# Sensor_Glove_Main-X02.net
KiCad netlist of a schematic drawn in Altium Designer
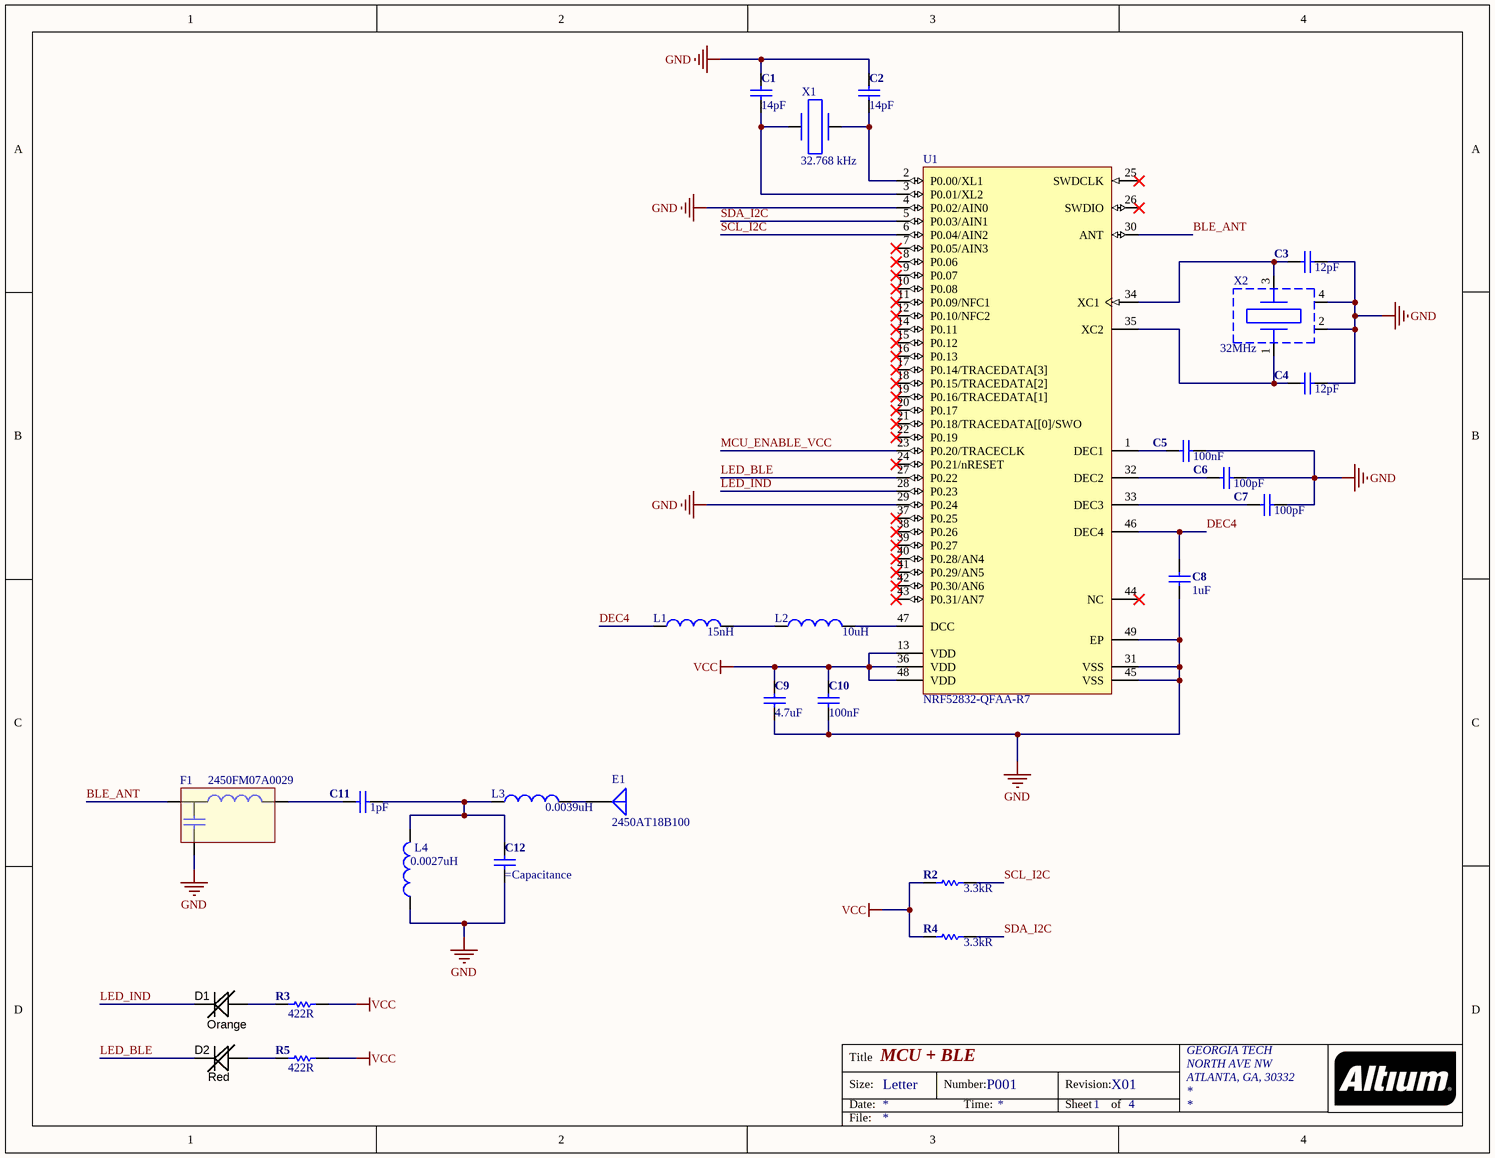
[diagram p0: Sensor_Glove_Main-X02.SchDoc]

(export (version "E")
  (design (tool "Eeschema 10.0.6"))
  (components
    (comp (ref "C1")
      (value "14pF")
      (footprint "C0402")
      (fields
        (field (name "MANUFACTURER") "Kyocera AVX")
        (field (name "MANUFACTURER PART NUMBER") "04025U140FAT2A")
        (field (name "TOLERANCE") "1%")
      )
      (libsource (lib "DB-X01") (part "C-0402(1005)"))
    )
    (comp (ref "C2")
      (value "14pF")
      (footprint "C0402")
      (fields
        (field (name "MANUFACTURER") "Kyocera AVX")
        (field (name "MANUFACTURER PART NUMBER") "04025U140FAT2A")
        (field (name "TOLERANCE") "1%")
      )
      (libsource (lib "DB-X01") (part "C-0402(1005)"))
    )
    (comp (ref "C3")
      (value "12pF")
      (footprint "C0402")
      (fields
        (field (name "MANUFACTURER") "Kyocera AVX")
        (field (name "MANUFACTURER PART NUMBER") "04025U120FAT2A")
        (field (name "TOLERANCE") "1%")
      )
      (libsource (lib "DB-X01") (part "C-0402(1005)"))
    )
    (comp (ref "C4")
      (value "12pF")
      (footprint "C0402")
      (fields
        (field (name "MANUFACTURER") "Kyocera AVX")
        (field (name "MANUFACTURER PART NUMBER") "04025U120FAT2A")
        (field (name "TOLERANCE") "1%")
      )
      (libsource (lib "DB-X01") (part "C-0402(1005)"))
    )
    (comp (ref "C5")
      (value "100nF")
      (footprint "C0402")
      (fields
        (field (name "MANUFACTURER") "Taiyo Yuden")
        (field (name "MANUFACTURER PART NUMBER") "TMK105BJ104KV-F")
        (field (name "TOLERANCE") "10%")
      )
      (libsource (lib "DB-X01") (part "C-0402(1005)"))
    )
    (comp (ref "C6")
      (value "100pF")
      (footprint "C0402")
      (fields
        (field (name "MANUFACTURER") "Yageo")
        (field (name "MANUFACTURER PART NUMBER") "CC0402FRNPO9BN101")
        (field (name "TOLERANCE") "1%")
      )
      (libsource (lib "DB-X01") (part "C-0402(1005)"))
    )
    (comp (ref "C7")
      (value "100pF")
      (footprint "C0402")
      (fields
        (field (name "MANUFACTURER") "Yageo")
        (field (name "MANUFACTURER PART NUMBER") "CC0402FRNPO9BN101")
        (field (name "TOLERANCE") "1%")
      )
      (libsource (lib "DB-X01") (part "C-0402(1005)"))
    )
    (comp (ref "C8")
      (value "1uF")
      (footprint "C0402")
      (fields
        (field (name "MANUFACTURER") "Yageo")
        (field (name "MANUFACTURER PART NUMBER") "CC0402MRX5R5BB105")
        (field (name "TOLERANCE") "20%")
      )
      (libsource (lib "DB-X01") (part "C-0402(1005)"))
    )
    (comp (ref "C9")
      (value "4.7uF")
      (footprint "C0402")
      (description "0402 10 V 4.7 uF ±20% Tolerance X5R Multilayer Ceramic Chip Capacitor")
      (fields
        (field (name "MANUFACTURER") "Murata")
        (field (name "MANUFACTURER PART NUMBER") "GRM155R61A475MEAAD")
      )
      (libsource (lib "DB-X01") (part "C-0402(1005)"))
    )
    (comp (ref "C10")
      (value "100nF")
      (footprint "C0402")
      (fields
        (field (name "MANUFACTURER") "Taiyo Yuden")
        (field (name "MANUFACTURER PART NUMBER") "TMK105BJ104KV-F")
        (field (name "TOLERANCE") "10%")
      )
      (libsource (lib "Sensor_Glove-X01") (part "C-0402(1005)"))
    )
    (comp (ref "C11")
      (value "1pF")
      (footprint "C0402")
      (fields
        (field (name "MANUFACTURER") "Murata")
        (field (name "MANUFACTURER PART NUMBER") "GCQ1555C1H1R0BB01D")
      )
      (libsource (lib "LP_ECG-X01") (part "C-0402(1005)"))
    )
    (comp (ref "C12") (value "~") (footprint "C0402") (libsource (lib "LP_ECG-X01") (part "C-0402(1005)")))
    (comp (ref "D1")
      (value "Orange")
      (footprint "LED_0402")
      (description "Single Color LED, Super Bright Orange, Water Clear, 0.8mm")
      (fields
        (field (name "MANUFACTURER") "Kingbright")
        (field (name "MANUFACTURER PART NUMBER") "APHHS1005SECK")
      )
      (libsource (lib "DB-X01") (part "LED_0402(1005)"))
    )
    (comp (ref "D2")
      (value "Red")
      (footprint "LED_0402")
      (description "Single Color LED, Hyper Red, Water Clear, 0.8mm")
      (fields
        (field (name "MANUFACTURER") "Kingbright")
        (field (name "MANUFACTURER PART NUMBER") "APHHS1005SURCK")
      )
      (libsource (lib "DB-X01") (part "LED_0402(1005)"))
    )
    (comp (ref "E1")
      (value "2450AT18B100")
      (footprint "2450AT18B100")
      (description "RF/Microwave Antenna, 2400MHz Min, 2500MHz Max")
      (fields
        (field (name "MANUFACTURER") "Johanson")
        (field (name "MANUFACTURER PART NUMBER") "2450AT18B100E")
      )
      (libsource (lib "LP_ECG-X01") (part "2450AT18B100"))
    )
    (comp (ref "F1")
      (value "2450FM07A0029")
      (footprint "2450FM07A0029")
      (description "Ceramic LPF")
      (fields
        (field (name "MANUFACTURER") "Johanson")
        (field (name "MANUFACTURER PART NUMBER") "2450FM07A0029T")
      )
      (libsource (lib "LP_ECG-X02") (part "2450FM07A0029"))
    )
    (comp (ref "L1")
      (value "15nH")
      (footprint "L0402")
      (description "General Purpose Inductor, 0.015uH, 5%, 1 Element, Ferrite-Core, SMD, 0402")
      (fields
        (field (name "MANUFACTURER") "Taiyo Yuden")
        (field (name "MANUFACTURER PART NUMBER") "HK100515NJ-T")
      )
      (libsource (lib "DB-X01") (part "I-0402(1005)"))
    )
    (comp (ref "L2")
      (value "10uH")
      (footprint "L0603")
      (description "General Purpose Inductor, 10uH, 10%, 1 Element, Ferrite-Core, SMD, 0603")
      (fields
        (field (name "MANUFACTURER") "Taiyo Yuden")
        (field (name "MANUFACTURER PART NUMBER") "CBMF1608T100K")
      )
      (libsource (lib "DB-X01") (part "I-0603(1608)"))
    )
    (comp (ref "L3")
      (value "0.0039uH")
      (footprint "L0402")
      (description "General Purpose Inductor, 0.0039uH, 5%, 1 Element, Ceramic-Core, SMD, 0402")
      (fields
        (field (name "MANUFACTURER") "Bourns")
        (field (name "MANUFACTURER PART NUMBER") "CW100505-3N9J")
      )
      (libsource (lib "LP_ECG-X01") (part "I-0402(1005)"))
    )
    (comp (ref "L4")
      (value "0.0027uH")
      (footprint "L0402")
      (description "General Purpose Inductor, 0.0027uH, 2%, 1 Element, SMD, 0402")
      (fields
        (field (name "MANUFACTURER") "Murata")
        (field (name "MANUFACTURER PART NUMBER") "LQW15AN2N7G8ZD")
      )
      (libsource (lib "LP_ECG-X01") (part "I-0402(1005)"))
    )
    (comp (ref "R2")
      (value "3.3kR")
      (footprint "R0402")
      (fields
        (field (name "MANUFACTURER") "Yageo")
        (field (name "MANUFACTURER PART NUMBER") "AC0402FR-073K3L")
        (field (name "TOLERANCE") "1%")
      )
      (libsource (lib "DB-X01") (part "R-0402(1005)"))
    )
    (comp (ref "R3")
      (value "422R")
      (footprint "R0402")
      (description "Fixed Resistor, Thin Film, 0.0625W, 422ohm, 50V, 0.1% +/-Tol, 25ppm/Cel, Surface Mount, 0402")
      (fields
        (field (name "MANUFACTURER") "Yageo")
        (field (name "MANUFACTURER PART NUMBER") "RT0402BRD07422RL")
      )
      (libsource (lib "DB-X01") (part "R-0402(1005)"))
    )
    (comp (ref "R4")
      (value "3.3kR")
      (footprint "R0402")
      (fields
        (field (name "MANUFACTURER") "Yageo")
        (field (name "MANUFACTURER PART NUMBER") "AC0402FR-073K3L")
        (field (name "TOLERANCE") "1%")
      )
      (libsource (lib "DB-X01") (part "R-0402(1005)"))
    )
    (comp (ref "R5")
      (value "422R")
      (footprint "R0402")
      (description "Fixed Resistor, Thin Film, 0.0625W, 422ohm, 50V, 0.1% +/-Tol, 25ppm/Cel, Surface Mount, 0402")
      (fields
        (field (name "MANUFACTURER") "Yageo")
        (field (name "MANUFACTURER PART NUMBER") "RT0402BRD07422RL")
      )
      (libsource (lib "DB-X01") (part "R-0402(1005)"))
    )
    (comp (ref "U1")
      (value "NRF52832-QFAA-R7")
      (footprint "NRF52832-QFAA-R7")
      (fields (field (name "MANUFACTURER") "Nordic Semiconductor"))
      (libsource (lib "DB-X01") (part "NRSC-NRF52832-QF-48"))
    )
    (comp (ref "X1")
      (value "32.768 kHz")
      (footprint "CRYSTAL_1MM2_X_1MM0")
      (description "Parallel - Fundamental Quartz Crystal, 0.032768MHz Nom")
      (fields
        (field (name "MANUFACTURER") "ECS International")
        (field (name "MANUFACTURER PART NUMBER") "ECS-.327-9-1210-TR")
      )
      (libsource (lib "DB-X01") (part "CRYSTAL_32K768"))
    )
    (comp (ref "X2")
      (value "32MHz")
      (footprint "CRYSTAL_1MM6_X_1MM2")
      (description "Parallel - Fundamental Quartz Crystal, 32MHz Nom")
      (fields (field (name "MANUFACTURER") "Diodes") (field (name "MANUFACTURER PART NUMBER") "US3200005Z"))
      (libsource (lib "DB-X01") (part "CRYSTAL_32MHz"))
    )
  )
  (nets
    (net (code "1") (name "/BLE_ANT") (class "Default")
      (node (ref "F1") (pin "1") (pinfunction "1_1") (pintype "passive"))
      (node (ref "U1") (pin "30") (pinfunction "ANT_30") (pintype "bidirectional"))
    )
    (net (code "2") (name "/DEC4") (class "Default")
      (node (ref "C8") (pin "2") (pinfunction "2_2") (pintype "passive"))
      (node (ref "L1") (pin "1") (pinfunction "1_1") (pintype "passive"))
      (node (ref "U1") (pin "46") (pinfunction "DEC4_46") (pintype "passive"))
    )
    (net (code "3") (name "/LED_BLE") (class "Default")
      (node (ref "D2") (pin "K") (pinfunction "K_K") (pintype "passive"))
      (node (ref "U1") (pin "27") (pinfunction "P0.22_27") (pintype "bidirectional"))
    )
    (net (code "4") (name "/LED_IND") (class "Default")
      (node (ref "D1") (pin "K") (pinfunction "K_K") (pintype "passive"))
      (node (ref "U1") (pin "28") (pinfunction "P0.23_28") (pintype "bidirectional"))
    )
    (net (code "5") (name "/MCU_ENABLE_VCC") (class "Default")
      (node (ref "U1") (pin "23") (pinfunction "P0.20/TRACECLK_23") (pintype "bidirectional"))
    )
    (net (code "6") (name "/SCL_I2C") (class "Default")
      (node (ref "R2") (pin "2") (pinfunction "2_2") (pintype "passive"))
      (node (ref "U1") (pin "6") (pinfunction "P0.04/AIN2_6") (pintype "bidirectional"))
    )
    (net (code "7") (name "/SDA_I2C") (class "Default")
      (node (ref "R4") (pin "2") (pinfunction "2_2") (pintype "passive"))
      (node (ref "U1") (pin "5") (pinfunction "P0.03/AIN1_5") (pintype "bidirectional"))
    )
    (net (code "8") (name "GND") (class "Default")
      (node (ref "C1") (pin "1") (pinfunction "1_1") (pintype "passive"))
      (node (ref "C10") (pin "1") (pinfunction "1_1") (pintype "passive"))
      (node (ref "C12") (pin "2") (pinfunction "2_2") (pintype "passive"))
      (node (ref "C2") (pin "1") (pinfunction "1_1") (pintype "passive"))
      (node (ref "C3") (pin "2") (pinfunction "2_2") (pintype "passive"))
      (node (ref "C4") (pin "2") (pinfunction "2_2") (pintype "passive"))
      (node (ref "C5") (pin "2") (pinfunction "2_2") (pintype "passive"))
      (node (ref "C6") (pin "2") (pinfunction "2_2") (pintype "passive"))
      (node (ref "C7") (pin "2") (pinfunction "2_2") (pintype "passive"))
      (node (ref "C8") (pin "1") (pinfunction "1_1") (pintype "passive"))
      (node (ref "C9") (pin "2") (pinfunction "2_2") (pintype "passive"))
      (node (ref "F1") (pin "3") (pinfunction "3_3") (pintype "passive"))
      (node (ref "L4") (pin "1") (pinfunction "1_1") (pintype "passive"))
      (node (ref "U1") (pin "29") (pinfunction "P0.24_29") (pintype "bidirectional"))
      (node (ref "U1") (pin "31") (pinfunction "VSS_31") (pintype "power_in"))
      (node (ref "U1") (pin "4") (pinfunction "P0.02/AIN0_4") (pintype "bidirectional"))
      (node (ref "U1") (pin "45") (pinfunction "VSS_45") (pintype "power_in"))
      (node (ref "U1") (pin "49") (pinfunction "EP_49") (pintype "power_in"))
      (node (ref "X2") (pin "2") (pinfunction "GND_2") (pintype "passive"))
      (node (ref "X2") (pin "4") (pinfunction "GND_4") (pintype "passive"))
    )
    (net (code "9") (name "Net-(C11-Pad1)") (class "Default")
      (node (ref "C11") (pin "1") (pinfunction "1_1") (pintype "passive"))
      (node (ref "F1") (pin "2") (pinfunction "2_2") (pintype "passive"))
    )
    (net (code "10") (name "Net-(C11-Pad2)") (class "Default")
      (node (ref "C11") (pin "2") (pinfunction "2_2") (pintype "passive"))
      (node (ref "C12") (pin "1") (pinfunction "1_1") (pintype "passive"))
      (node (ref "L3") (pin "1") (pinfunction "1_1") (pintype "passive"))
      (node (ref "L4") (pin "2") (pinfunction "2_2") (pintype "passive"))
    )
    (net (code "11") (name "Net-(D1-PadA)") (class "Default")
      (node (ref "D1") (pin "A") (pinfunction "A_A") (pintype "passive"))
      (node (ref "R3") (pin "2") (pinfunction "2_2") (pintype "passive"))
    )
    (net (code "12") (name "Net-(D2-PadA)") (class "Default")
      (node (ref "D2") (pin "A") (pinfunction "A_A") (pintype "passive"))
      (node (ref "R5") (pin "2") (pinfunction "2_2") (pintype "passive"))
    )
    (net (code "13") (name "Net-(E1-A)") (class "Default")
      (node (ref "E1") (pin "1") (pinfunction "A_1") (pintype "passive"))
      (node (ref "L3") (pin "2") (pinfunction "2_2") (pintype "passive"))
    )
    (net (code "14") (name "Net-(L1-Pad2)") (class "Default")
      (node (ref "L1") (pin "2") (pinfunction "2_2") (pintype "passive"))
      (node (ref "L2") (pin "1") (pinfunction "1_1") (pintype "passive"))
    )
    (net (code "15") (name "Net-(U1-DCC)") (class "Default")
      (node (ref "L2") (pin "2") (pinfunction "2_2") (pintype "passive"))
      (node (ref "U1") (pin "47") (pinfunction "DCC_47") (pintype "power_in"))
    )
    (net (code "16") (name "Net-(U1-DEC1)") (class "Default")
      (node (ref "C5") (pin "1") (pinfunction "1_1") (pintype "passive"))
      (node (ref "U1") (pin "1") (pinfunction "DEC1_1") (pintype "passive"))
    )
    (net (code "17") (name "Net-(U1-DEC2)") (class "Default")
      (node (ref "C6") (pin "1") (pinfunction "1_1") (pintype "passive"))
      (node (ref "U1") (pin "32") (pinfunction "DEC2_32") (pintype "passive"))
    )
    (net (code "18") (name "Net-(U1-DEC3)") (class "Default")
      (node (ref "C7") (pin "1") (pinfunction "1_1") (pintype "passive"))
      (node (ref "U1") (pin "33") (pinfunction "DEC3_33") (pintype "passive"))
    )
    (net (code "19") (name "Net-(U1-P0.00{slash}XL1)") (class "Default")
      (node (ref "C2") (pin "2") (pinfunction "2_2") (pintype "passive"))
      (node (ref "U1") (pin "2") (pinfunction "P0.00/XL1_2") (pintype "bidirectional"))
      (node (ref "X1") (pin "2") (pinfunction "2_2") (pintype "passive"))
    )
    (net (code "20") (name "Net-(U1-P0.01{slash}XL2)") (class "Default")
      (node (ref "C1") (pin "2") (pinfunction "2_2") (pintype "passive"))
      (node (ref "U1") (pin "3") (pinfunction "P0.01/XL2_3") (pintype "bidirectional"))
      (node (ref "X1") (pin "1") (pinfunction "1_1") (pintype "passive"))
    )
    (net (code "21") (name "Net-(U1-XC1)") (class "Default")
      (node (ref "C3") (pin "1") (pinfunction "1_1") (pintype "passive"))
      (node (ref "U1") (pin "34") (pinfunction "XC1_34") (pintype "input"))
      (node (ref "X2") (pin "3") (pinfunction "3_3") (pintype "passive"))
    )
    (net (code "22") (name "Net-(U1-XC2)") (class "Default")
      (node (ref "C4") (pin "1") (pinfunction "1_1") (pintype "passive"))
      (node (ref "U1") (pin "35") (pinfunction "XC2_35") (pintype "passive"))
      (node (ref "X2") (pin "1") (pinfunction "1_1") (pintype "passive"))
    )
    (net (code "23") (name "VCC") (class "Default")
      (node (ref "C10") (pin "2") (pinfunction "2_2") (pintype "passive"))
      (node (ref "C9") (pin "1") (pinfunction "1_1") (pintype "passive"))
      (node (ref "R2") (pin "1") (pinfunction "1_1") (pintype "passive"))
      (node (ref "R3") (pin "1") (pinfunction "1_1") (pintype "passive"))
      (node (ref "R4") (pin "1") (pinfunction "1_1") (pintype "passive"))
      (node (ref "R5") (pin "1") (pinfunction "1_1") (pintype "passive"))
      (node (ref "U1") (pin "13") (pinfunction "VDD_13") (pintype "power_in"))
      (node (ref "U1") (pin "36") (pinfunction "VDD_36") (pintype "power_in"))
      (node (ref "U1") (pin "48") (pinfunction "VDD_48") (pintype "power_in"))
    )
    (net (code "24") (name "unconnected-(U1-NC-Pad44)") (class "Default")
      (node (ref "U1") (pin "44") (pinfunction "NC_44") (pintype "passive+no_connect"))
    )
    (net (code "25") (name "unconnected-(U1-P0.05{slash}AIN3-Pad7)") (class "Default")
      (node (ref "U1") (pin "7") (pinfunction "P0.05/AIN3_7") (pintype "bidirectional+no_connect"))
    )
    (net (code "26") (name "unconnected-(U1-P0.06-Pad8)") (class "Default")
      (node (ref "U1") (pin "8") (pinfunction "P0.06_8") (pintype "bidirectional+no_connect"))
    )
    (net (code "27") (name "unconnected-(U1-P0.07-Pad9)") (class "Default")
      (node (ref "U1") (pin "9") (pinfunction "P0.07_9") (pintype "bidirectional+no_connect"))
    )
    (net (code "28") (name "unconnected-(U1-P0.08-Pad10)") (class "Default")
      (node (ref "U1") (pin "10") (pinfunction "P0.08_10") (pintype "bidirectional+no_connect"))
    )
    (net (code "29") (name "unconnected-(U1-P0.09{slash}NFC1-Pad11)") (class "Default")
      (node (ref "U1") (pin "11") (pinfunction "P0.09/NFC1_11") (pintype "bidirectional+no_connect"))
    )
    (net (code "30") (name "unconnected-(U1-P0.10{slash}NFC2-Pad12)") (class "Default")
      (node (ref "U1") (pin "12") (pinfunction "P0.10/NFC2_12") (pintype "bidirectional+no_connect"))
    )
    (net (code "31") (name "unconnected-(U1-P0.11-Pad14)") (class "Default")
      (node (ref "U1") (pin "14") (pinfunction "P0.11_14") (pintype "bidirectional+no_connect"))
    )
    (net (code "32") (name "unconnected-(U1-P0.12-Pad15)") (class "Default")
      (node (ref "U1") (pin "15") (pinfunction "P0.12_15") (pintype "bidirectional+no_connect"))
    )
    (net (code "33") (name "unconnected-(U1-P0.13-Pad16)") (class "Default")
      (node (ref "U1") (pin "16") (pinfunction "P0.13_16") (pintype "bidirectional+no_connect"))
    )
    (net (code "34") (name "unconnected-(U1-P0.14{slash}TRACEDATA[3]-Pad17)") (class "Default")
      (node (ref "U1") (pin "17") (pinfunction "P0.14/TRACEDATA[3]_17") (pintype "bidirectional+no_connect"))
    )
    (net (code "35") (name "unconnected-(U1-P0.15{slash}TRACEDATA[2]-Pad18)") (class "Default")
      (node (ref "U1") (pin "18") (pinfunction "P0.15/TRACEDATA[2]_18") (pintype "bidirectional+no_connect"))
    )
    (net (code "36") (name "unconnected-(U1-P0.16{slash}TRACEDATA[1]-Pad19)") (class "Default")
      (node (ref "U1") (pin "19") (pinfunction "P0.16/TRACEDATA[1]_19") (pintype "bidirectional+no_connect"))
    )
    (net (code "37") (name "unconnected-(U1-P0.17-Pad20)") (class "Default")
      (node (ref "U1") (pin "20") (pinfunction "P0.17_20") (pintype "bidirectional+no_connect"))
    )
    (net (code "38") (name "unconnected-(U1-P0.18{slash}TRACEDATA[[0]{slash}SWO-Pad21)") (class "Default")
      (node (ref "U1") (pin "21") (pinfunction "P0.18/TRACEDATA[[0]/SWO_21") (pintype "bidirectional+no_connect"))
    )
    (net (code "39") (name "unconnected-(U1-P0.19-Pad22)") (class "Default")
      (node (ref "U1") (pin "22") (pinfunction "P0.19_22") (pintype "bidirectional+no_connect"))
    )
    (net (code "40") (name "unconnected-(U1-P0.21{slash}nRESET-Pad24)") (class "Default")
      (node (ref "U1") (pin "24") (pinfunction "P0.21/nRESET_24") (pintype "bidirectional+no_connect"))
    )
    (net (code "41") (name "unconnected-(U1-P0.25-Pad37)") (class "Default")
      (node (ref "U1") (pin "37") (pinfunction "P0.25_37") (pintype "bidirectional+no_connect"))
    )
    (net (code "42") (name "unconnected-(U1-P0.26-Pad38)") (class "Default")
      (node (ref "U1") (pin "38") (pinfunction "P0.26_38") (pintype "bidirectional+no_connect"))
    )
    (net (code "43") (name "unconnected-(U1-P0.27-Pad39)") (class "Default")
      (node (ref "U1") (pin "39") (pinfunction "P0.27_39") (pintype "bidirectional+no_connect"))
    )
    (net (code "44") (name "unconnected-(U1-P0.28{slash}AN4-Pad40)") (class "Default")
      (node (ref "U1") (pin "40") (pinfunction "P0.28/AN4_40") (pintype "bidirectional+no_connect"))
    )
    (net (code "45") (name "unconnected-(U1-P0.29{slash}AN5-Pad41)") (class "Default")
      (node (ref "U1") (pin "41") (pinfunction "P0.29/AN5_41") (pintype "bidirectional+no_connect"))
    )
    (net (code "46") (name "unconnected-(U1-P0.30{slash}AN6-Pad42)") (class "Default")
      (node (ref "U1") (pin "42") (pinfunction "P0.30/AN6_42") (pintype "bidirectional+no_connect"))
    )
    (net (code "47") (name "unconnected-(U1-P0.31{slash}AN7-Pad43)") (class "Default")
      (node (ref "U1") (pin "43") (pinfunction "P0.31/AN7_43") (pintype "bidirectional+no_connect"))
    )
    (net (code "48") (name "unconnected-(U1-SWDCLK-Pad25)") (class "Default")
      (node (ref "U1") (pin "25") (pinfunction "SWDCLK_25") (pintype "input+no_connect"))
    )
    (net (code "49") (name "unconnected-(U1-SWDIO-Pad26)") (class "Default")
      (node (ref "U1") (pin "26") (pinfunction "SWDIO_26") (pintype "bidirectional+no_connect"))
    )
  )
)
